# scanner_board_TOP.net
KiCad netlist of a schematic drawn in Altium Designer
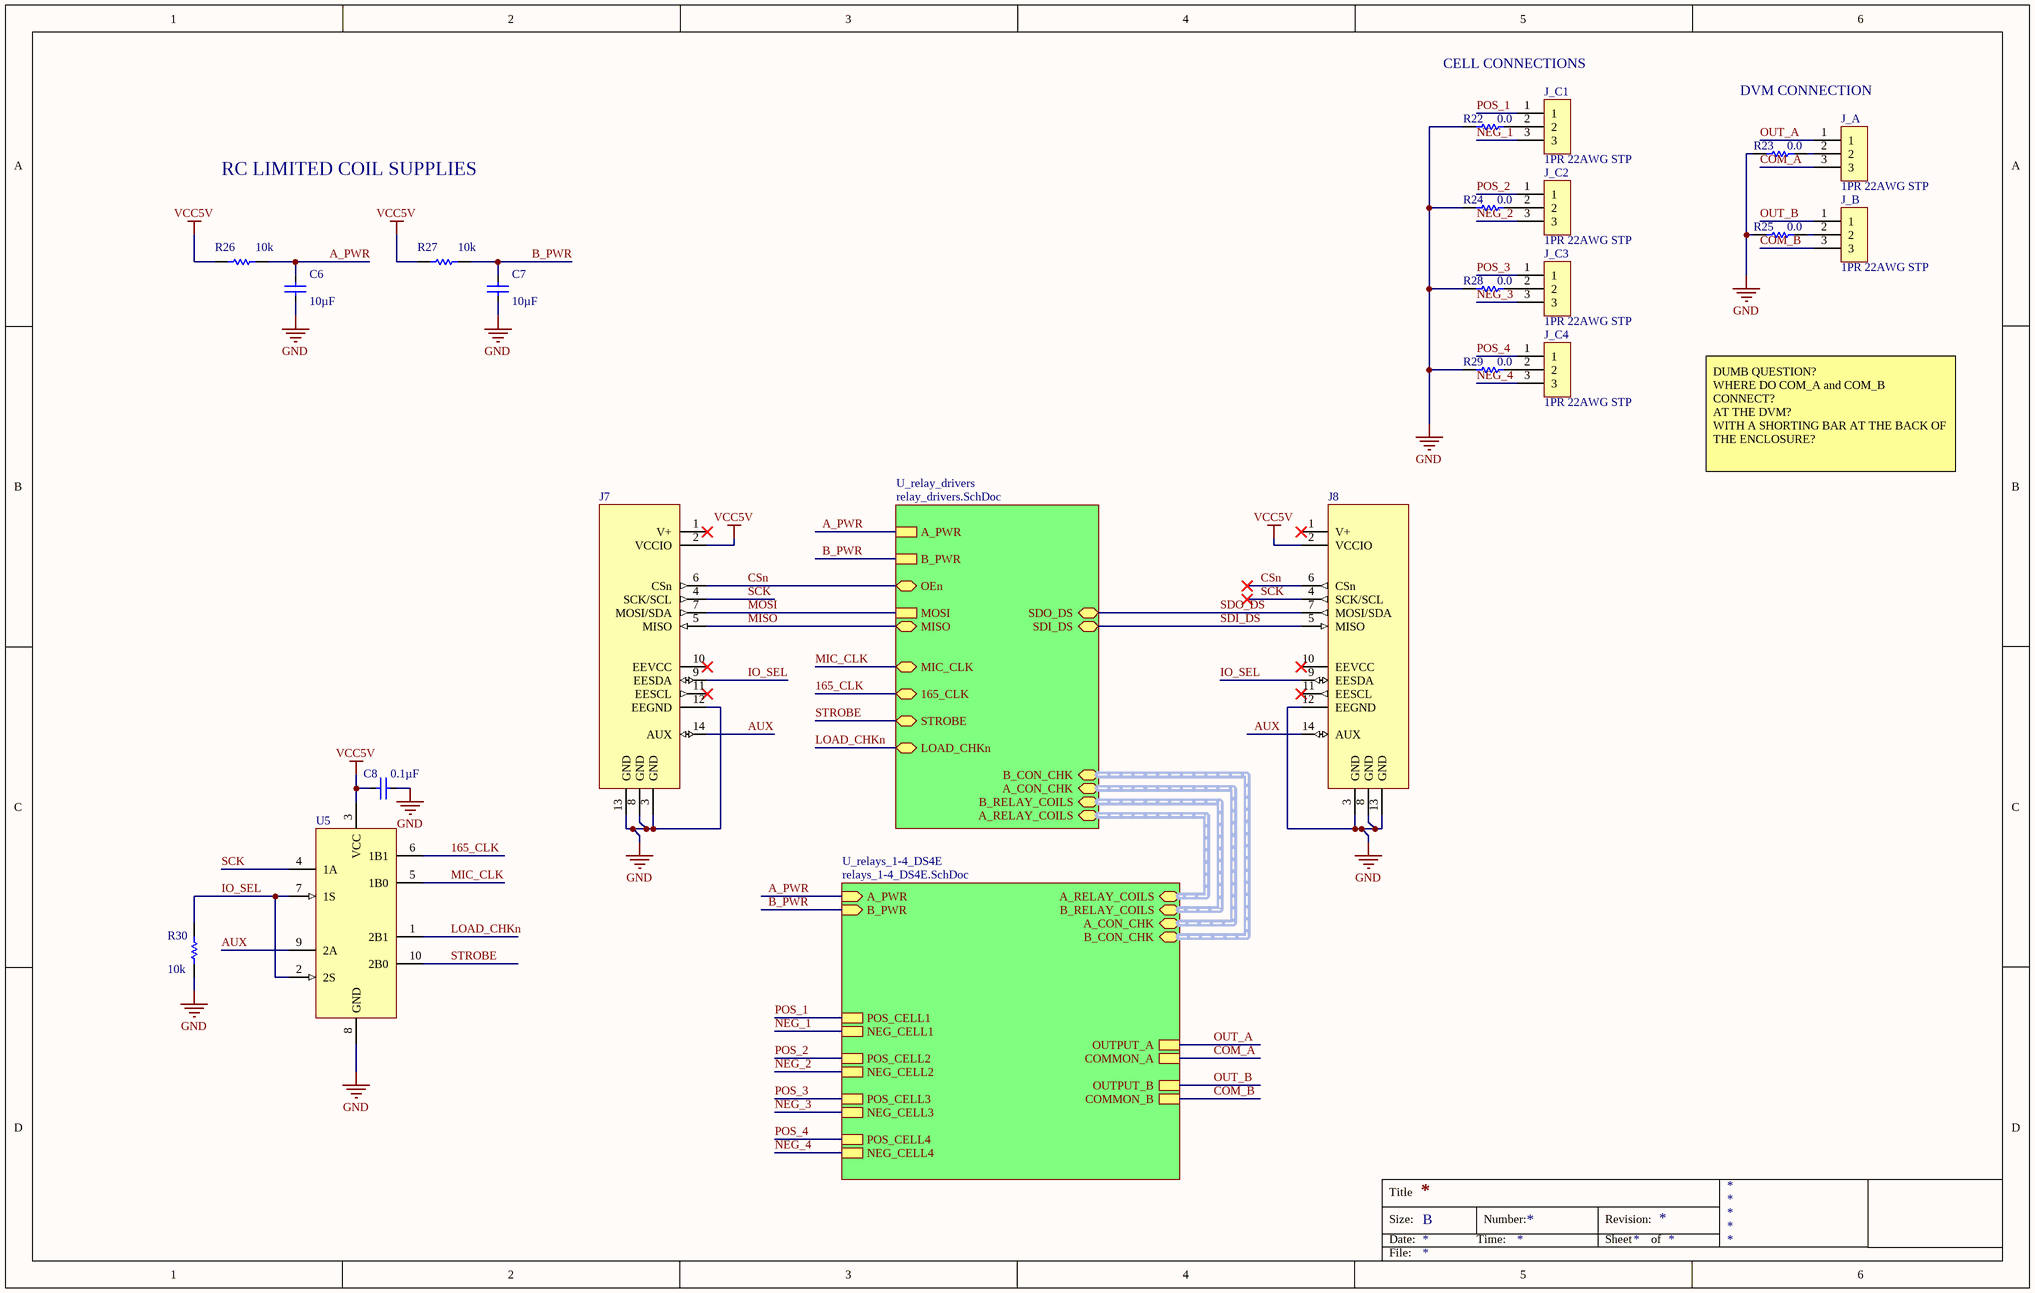
[diagram p0: scanner_board_TOP.SchDoc]

(export (version "E")
  (design (tool "Eeschema 10.0.6"))
  (components
    (comp (ref "C6")
      (value "10µF")
      (footprint "CAPC3216X160L55N")
      (description "CAP CER 10UF 25V X7R 1206")
      (fields
        (field (name "MANUFACTURER") "Murata Electronics North America")
        (field (name "MANUFACTURER PART NUMBER") "GRM31CR71E106KA12L")
      )
      (libsource (lib "mechanart_oshw") (part "CapSMT"))
    )
    (comp (ref "C7")
      (value "10µF")
      (footprint "CAPC3216X160L55N")
      (description "CAP CER 10UF 25V X7R 1206")
      (fields
        (field (name "MANUFACTURER") "Murata Electronics North America")
        (field (name "MANUFACTURER PART NUMBER") "GRM31CR71E106KA12L")
      )
      (libsource (lib "mechanart_oshw") (part "CapSMT"))
    )
    (comp (ref "C8")
      (value "0.1µF")
      (footprint "CAPC1005X55L25N")
      (description "CAP CER 0.1UF 16V X7R 0402")
      (fields
        (field (name "MANUFACTURER") "Murata Electronics North America")
        (field (name "MANUFACTURER PART NUMBER") "GRM155R71C104JA88D")
      )
      (libsource (lib "mechanart_oshw") (part "CapSMT"))
    )
    (comp (ref "J7")
      (value "QUIKEVAL_HEADER")
      (footprint "0878311420")
      (description "CONN HEADER 14POS 2MM VERT GOLD")
      (fields
        (field (name "MANUFACTURER") "Molex, LLC")
        (field (name "MANUFACTURER PART NUMBER") "0878311420")
      )
      (libsource (lib "") (part "QUIKEVAL_HEADER_1"))
    )
    (comp (ref "J8")
      (value "QUIKEVAL_HEADER")
      (footprint "0878311420")
      (description "CONN HEADER 14POS 2MM VERT GOLD")
      (fields
        (field (name "MANUFACTURER") "Molex, LLC")
        (field (name "MANUFACTURER PART NUMBER") "0878311420")
      )
      (libsource (lib "mechanart_oshw") (part "QUIKEVAL_HEADER"))
    )
    (comp (ref "J_A")
      (value "1PR 22AWG STP")
      (footprint "HDRV3W25P100_3X1_300X100H500")
      (description "SOLDER HOLES FOR 3 22AWG WIRES")
      (libsource (lib "mechanart_oshw") (part "HEADER_3"))
    )
    (comp (ref "J_B")
      (value "1PR 22AWG STP")
      (footprint "HDRV3W25P100_3X1_300X100H500")
      (description "SOLDER HOLES FOR 3 22AWG WIRES")
      (libsource (lib "mechanart_oshw") (part "HEADER_3"))
    )
    (comp (ref "J_C1")
      (value "1PR 22AWG STP")
      (footprint "HDRV3W25P100_3X1_300X100H500")
      (description "SOLDER HOLES FOR 3 22AWG WIRES")
      (libsource (lib "mechanart_oshw") (part "HEADER_3"))
    )
    (comp (ref "J_C2")
      (value "1PR 22AWG STP")
      (footprint "HDRV3W25P100_3X1_300X100H500")
      (description "SOLDER HOLES FOR 3 22AWG WIRES")
      (libsource (lib "mechanart_oshw") (part "HEADER_3"))
    )
    (comp (ref "J_C3")
      (value "1PR 22AWG STP")
      (footprint "HDRV3W25P100_3X1_300X100H500")
      (description "SOLDER HOLES FOR 3 22AWG WIRES")
      (libsource (lib "mechanart_oshw") (part "HEADER_3"))
    )
    (comp (ref "J_C4")
      (value "1PR 22AWG STP")
      (footprint "HDRV3W25P100_3X1_300X100H500")
      (description "SOLDER HOLES FOR 3 22AWG WIRES")
      (libsource (lib "mechanart_oshw") (part "HEADER_3"))
    )
    (comp (ref "R22")
      (value "0.0")
      (footprint "RESC2012X75L55N")
      (description "RES SMD 0.03 OHM 1% 1/2W 0805")
      (fields
        (field (name "MANUFACTURER") "Panasonic Electronic Components")
        (field (name "MANUFACTURER PART NUMBER") "ERJ-6BWFR030V")
      )
      (libsource (lib "mechanart_oshw") (part "ResSMT"))
    )
    (comp (ref "R23")
      (value "0.0")
      (footprint "RESC2012X75L55N")
      (description "RES SMD 0.03 OHM 1% 1/2W 0805")
      (fields
        (field (name "MANUFACTURER") "Panasonic Electronic Components")
        (field (name "MANUFACTURER PART NUMBER") "ERJ-6BWFR030V")
      )
      (libsource (lib "mechanart_oshw") (part "ResSMT"))
    )
    (comp (ref "R24")
      (value "0.0")
      (footprint "RESC2012X75L55N")
      (description "RES SMD 0.03 OHM 1% 1/2W 0805")
      (fields
        (field (name "MANUFACTURER") "Panasonic Electronic Components")
        (field (name "MANUFACTURER PART NUMBER") "ERJ-6BWFR030V")
      )
      (libsource (lib "mechanart_oshw") (part "ResSMT"))
    )
    (comp (ref "R25")
      (value "0.0")
      (footprint "RESC2012X75L55N")
      (description "RES SMD 0.03 OHM 1% 1/2W 0805")
      (fields
        (field (name "MANUFACTURER") "Panasonic Electronic Components")
        (field (name "MANUFACTURER PART NUMBER") "ERJ-6BWFR030V")
      )
      (libsource (lib "mechanart_oshw") (part "ResSMT"))
    )
    (comp (ref "R26")
      (value "10k")
      (footprint "RESC_3216[1206]_N")
      (description "RES SMD 10K OHM 5% 1/4W 1206")
      (fields
        (field (name "MANUFACTURER") "Vishay Dale")
        (field (name "MANUFACTURER PART NUMBER") "CRCW120610K0JNEA")
      )
      (libsource (lib "mechanart_oshw") (part "ResSMT"))
    )
    (comp (ref "R27")
      (value "10k")
      (footprint "RESC_3216[1206]_N")
      (description "RES SMD 10K OHM 5% 1/4W 1206")
      (fields
        (field (name "MANUFACTURER") "Vishay Dale")
        (field (name "MANUFACTURER PART NUMBER") "CRCW120610K0JNEA")
      )
      (libsource (lib "mechanart_oshw") (part "ResSMT"))
    )
    (comp (ref "R28")
      (value "0.0")
      (footprint "RESC2012X75L55N")
      (description "RES SMD 0.03 OHM 1% 1/2W 0805")
      (fields
        (field (name "MANUFACTURER") "Panasonic Electronic Components")
        (field (name "MANUFACTURER PART NUMBER") "ERJ-6BWFR030V")
      )
      (libsource (lib "mechanart_oshw") (part "ResSMT"))
    )
    (comp (ref "R29")
      (value "0.0")
      (footprint "RESC2012X75L55N")
      (description "RES SMD 0.03 OHM 1% 1/2W 0805")
      (fields
        (field (name "MANUFACTURER") "Panasonic Electronic Components")
        (field (name "MANUFACTURER PART NUMBER") "ERJ-6BWFR030V")
      )
      (libsource (lib "mechanart_oshw") (part "ResSMT"))
    )
    (comp (ref "R30")
      (value "10k")
      (footprint "RESC2012X75L55N")
      (description "RES SMD 10K OHM 5% 1/2W 0805")
      (fields
        (field (name "MANUFACTURER") "Panasonic Electronic Components")
        (field (name "MANUFACTURER PART NUMBER") "ERJ-P06J103V")
      )
      (libsource (lib "mechanart_oshw") (part "ResSMT"))
    )
    (comp (ref "U5")
      (value "FSA2257MUX")
      (footprint "SOP50P490X110-10L30N")
      (description "IC SWITCH DUAL SPDT 10MSOP")
      (fields (field (name "MANUFACTURER") "Fairchild/ON Semiconductor"))
      (libsource (lib "mechanart_oshw") (part "FSA2257MUX"))
    )
  )
  (nets
    (net (code "1") (name "/165_CLK") (class "Default")
      (node (ref "U5") (pin "6") (pinfunction "1B1_6") (pintype "passive"))
    )
    (net (code "2") (name "/AUX") (class "Default")
      (node (ref "J7") (pin "14") (pinfunction "AUX_14") (pintype "bidirectional"))
      (node (ref "J8") (pin "14") (pinfunction "AUX_14") (pintype "bidirectional"))
      (node (ref "U5") (pin "9") (pinfunction "2A_9") (pintype "passive"))
    )
    (net (code "4") (name "/A_PWR") (class "Default")
      (node (ref "C6") (pin "1") (pinfunction "1_1") (pintype "passive"))
      (node (ref "R26") (pin "2") (pinfunction "2_2") (pintype "passive"))
    )
    (net (code "7") (name "/B_PWR") (class "Default")
      (node (ref "C7") (pin "1") (pinfunction "1_1") (pintype "passive"))
      (node (ref "R27") (pin "2") (pinfunction "2_2") (pintype "passive"))
    )
    (net (code "9") (name "/COM_A") (class "Default")
      (node (ref "J_A") (pin "3") (pinfunction "3_3") (pintype "passive"))
    )
    (net (code "10") (name "/COM_B") (class "Default")
      (node (ref "J_B") (pin "3") (pinfunction "3_3") (pintype "passive"))
    )
    (net (code "11") (name "/CSn") (class "Default")
      (node (ref "J7") (pin "6") (pinfunction "CSn_6") (pintype "output"))
      (node (ref "J8") (pin "6") (pinfunction "CSn_6") (pintype "output"))
    )
    (net (code "12") (name "/IO_SEL") (class "Default")
      (node (ref "J7") (pin "9") (pinfunction "EESDA_9") (pintype "bidirectional"))
      (node (ref "J8") (pin "9") (pinfunction "EESDA_9") (pintype "bidirectional"))
      (node (ref "R30") (pin "2") (pinfunction "2_2") (pintype "passive"))
      (node (ref "U5") (pin "2") (pinfunction "2S_2") (pintype "input"))
      (node (ref "U5") (pin "7") (pinfunction "1S_7") (pintype "input"))
    )
    (net (code "13") (name "/LOAD_CHKn") (class "Default")
      (node (ref "U5") (pin "1") (pinfunction "2B1_1") (pintype "passive"))
    )
    (net (code "14") (name "/MIC_CLK") (class "Default")
      (node (ref "U5") (pin "5") (pinfunction "1B0_5") (pintype "passive"))
    )
    (net (code "15") (name "/MISO") (class "Default")
      (node (ref "J7") (pin "5") (pinfunction "MISO_5") (pintype "input"))
    )
    (net (code "16") (name "/MOSI") (class "Default")
      (node (ref "J7") (pin "7") (pinfunction "MOSI/SDA_7") (pintype "output"))
    )
    (net (code "17") (name "/NEG_1") (class "Default")
      (node (ref "J_C1") (pin "3") (pinfunction "3_3") (pintype "passive"))
    )
    (net (code "18") (name "/NEG_2") (class "Default")
      (node (ref "J_C2") (pin "3") (pinfunction "3_3") (pintype "passive"))
    )
    (net (code "19") (name "/NEG_3") (class "Default")
      (node (ref "J_C3") (pin "3") (pinfunction "3_3") (pintype "passive"))
    )
    (net (code "20") (name "/NEG_4") (class "Default")
      (node (ref "J_C4") (pin "3") (pinfunction "3_3") (pintype "passive"))
    )
    (net (code "21") (name "/OUT_A") (class "Default")
      (node (ref "J_A") (pin "1") (pinfunction "1_1") (pintype "passive"))
    )
    (net (code "22") (name "/OUT_B") (class "Default")
      (node (ref "J_B") (pin "1") (pinfunction "1_1") (pintype "passive"))
    )
    (net (code "23") (name "/POS_1") (class "Default")
      (node (ref "J_C1") (pin "1") (pinfunction "1_1") (pintype "passive"))
    )
    (net (code "24") (name "/POS_2") (class "Default")
      (node (ref "J_C2") (pin "1") (pinfunction "1_1") (pintype "passive"))
    )
    (net (code "25") (name "/POS_3") (class "Default")
      (node (ref "J_C3") (pin "1") (pinfunction "1_1") (pintype "passive"))
    )
    (net (code "26") (name "/POS_4") (class "Default")
      (node (ref "J_C4") (pin "1") (pinfunction "1_1") (pintype "passive"))
    )
    (net (code "27") (name "/SCK") (class "Default")
      (node (ref "J7") (pin "4") (pinfunction "SCK/SCL_4") (pintype "output"))
      (node (ref "J8") (pin "4") (pinfunction "SCK/SCL_4") (pintype "output"))
      (node (ref "U5") (pin "4") (pinfunction "1A_4") (pintype "passive"))
    )
    (net (code "28") (name "/SDI_DS") (class "Default")
      (node (ref "J8") (pin "5") (pinfunction "MISO_5") (pintype "input"))
    )
    (net (code "29") (name "/SDO_DS") (class "Default")
      (node (ref "J8") (pin "7") (pinfunction "MOSI/SDA_7") (pintype "output"))
    )
    (net (code "30") (name "/STROBE") (class "Default")
      (node (ref "U5") (pin "10") (pinfunction "2B0_10") (pintype "passive"))
    )
    (net (code "31") (name "GND") (class "Default")
      (node (ref "C6") (pin "2") (pinfunction "2_2") (pintype "passive"))
      (node (ref "C7") (pin "2") (pinfunction "2_2") (pintype "passive"))
      (node (ref "C8") (pin "2") (pinfunction "2_2") (pintype "passive"))
      (node (ref "J7") (pin "12") (pinfunction "EEGND_12") (pintype "power_in"))
      (node (ref "J7") (pin "13") (pinfunction "GND_13") (pintype "power_in"))
      (node (ref "J7") (pin "3") (pinfunction "GND_3") (pintype "power_in"))
      (node (ref "J7") (pin "8") (pinfunction "GND_8") (pintype "power_in"))
      (node (ref "J8") (pin "12") (pinfunction "EEGND_12") (pintype "power_in"))
      (node (ref "J8") (pin "13") (pinfunction "GND_13") (pintype "power_in"))
      (node (ref "J8") (pin "3") (pinfunction "GND_3") (pintype "power_in"))
      (node (ref "J8") (pin "8") (pinfunction "GND_8") (pintype "power_in"))
      (node (ref "R22") (pin "2") (pinfunction "2_2") (pintype "passive"))
      (node (ref "R23") (pin "2") (pinfunction "2_2") (pintype "passive"))
      (node (ref "R24") (pin "2") (pinfunction "2_2") (pintype "passive"))
      (node (ref "R25") (pin "2") (pinfunction "2_2") (pintype "passive"))
      (node (ref "R28") (pin "2") (pinfunction "2_2") (pintype "passive"))
      (node (ref "R29") (pin "2") (pinfunction "2_2") (pintype "passive"))
      (node (ref "R30") (pin "1") (pinfunction "1_1") (pintype "passive"))
      (node (ref "U5") (pin "8") (pinfunction "GND_8") (pintype "power_in"))
    )
    (net (code "32") (name "Net-(J_A-Pad2)") (class "Default")
      (node (ref "J_A") (pin "2") (pinfunction "2_2") (pintype "passive"))
      (node (ref "R23") (pin "1") (pinfunction "1_1") (pintype "passive"))
    )
    (net (code "33") (name "Net-(J_B-Pad2)") (class "Default")
      (node (ref "J_B") (pin "2") (pinfunction "2_2") (pintype "passive"))
      (node (ref "R25") (pin "1") (pinfunction "1_1") (pintype "passive"))
    )
    (net (code "34") (name "Net-(J_C1-Pad2)") (class "Default")
      (node (ref "J_C1") (pin "2") (pinfunction "2_2") (pintype "passive"))
      (node (ref "R22") (pin "1") (pinfunction "1_1") (pintype "passive"))
    )
    (net (code "35") (name "Net-(J_C2-Pad2)") (class "Default")
      (node (ref "J_C2") (pin "2") (pinfunction "2_2") (pintype "passive"))
      (node (ref "R24") (pin "1") (pinfunction "1_1") (pintype "passive"))
    )
    (net (code "36") (name "Net-(J_C3-Pad2)") (class "Default")
      (node (ref "J_C3") (pin "2") (pinfunction "2_2") (pintype "passive"))
      (node (ref "R28") (pin "1") (pinfunction "1_1") (pintype "passive"))
    )
    (net (code "37") (name "Net-(J_C4-Pad2)") (class "Default")
      (node (ref "J_C4") (pin "2") (pinfunction "2_2") (pintype "passive"))
      (node (ref "R29") (pin "1") (pinfunction "1_1") (pintype "passive"))
    )
    (net (code "38") (name "VCC5V") (class "Default")
      (node (ref "C8") (pin "1") (pinfunction "1_1") (pintype "passive"))
      (node (ref "J7") (pin "2") (pinfunction "VCCIO_2") (pintype "power_in"))
      (node (ref "J8") (pin "2") (pinfunction "VCCIO_2") (pintype "power_in"))
      (node (ref "R26") (pin "1") (pinfunction "1_1") (pintype "passive"))
      (node (ref "R27") (pin "1") (pinfunction "1_1") (pintype "passive"))
      (node (ref "U5") (pin "3") (pinfunction "VCC_3") (pintype "power_in"))
    )
    (net (code "39") (name "unconnected-(J7-EESCL-Pad11)") (class "Default")
      (node (ref "J7") (pin "11") (pinfunction "EESCL_11") (pintype "output+no_connect"))
    )
    (net (code "40") (name "unconnected-(J7-EEVCC-Pad10)") (class "Default")
      (node (ref "J7") (pin "10") (pinfunction "EEVCC_10") (pintype "power_in+no_connect"))
    )
    (net (code "41") (name "unconnected-(J7-V+-Pad1)") (class "Default")
      (node (ref "J7") (pin "1") (pinfunction "V+_1") (pintype "power_in+no_connect"))
    )
    (net (code "42") (name "unconnected-(J8-EESCL-Pad11)") (class "Default")
      (node (ref "J8") (pin "11") (pinfunction "EESCL_11") (pintype "output+no_connect"))
    )
    (net (code "43") (name "unconnected-(J8-EEVCC-Pad10)") (class "Default")
      (node (ref "J8") (pin "10") (pinfunction "EEVCC_10") (pintype "power_in+no_connect"))
    )
    (net (code "44") (name "unconnected-(J8-V+-Pad1)") (class "Default")
      (node (ref "J8") (pin "1") (pinfunction "V+_1") (pintype "power_in+no_connect"))
    )
  )
)
